# Dual_signal_switch.net
KiCad netlist of a schematic drawn in Altium Designer
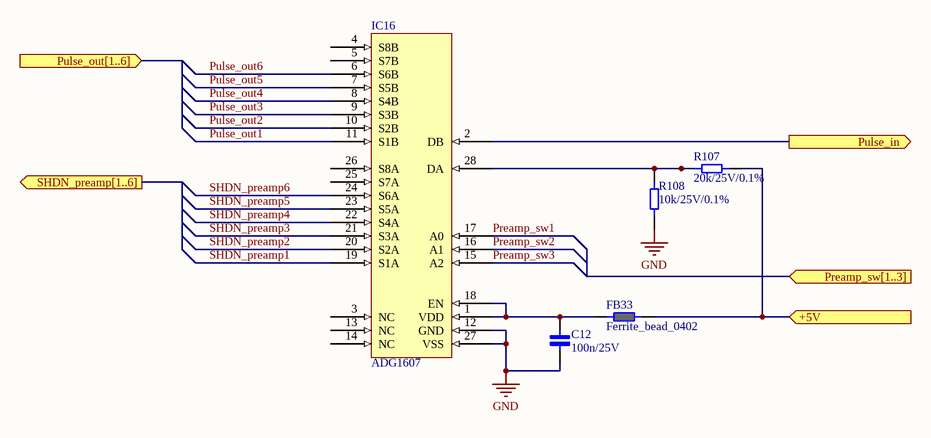
[diagram p0: Dual_signal_switch.SchDoc]

(export (version "E")
  (design (tool "Eeschema 10.0.6"))
  (components
    (comp (ref "C12")
      (value "100n/25V")
      (footprint "Cap_0402")
      (description "Ceramic Capacitor 100n / 0402 / 25V / ±5%, Wurth Elektronik MLCC")
      (libsource (lib "Cubesat_lib") (part "Cap_0402_100n"))
    )
    (comp (ref "FB33")
      (value "Ferrite_bead_0402")
      (footprint "FERRITE_0402")
      (description "Ferrite bead, wurth 74269241102")
      (libsource (lib "Cubesat_lib") (part "Ferrite_bead_0402"))
    )
    (comp (ref "IC16")
      (value "ADG1607")
      (footprint "TSOP28")
      (description "8-ch MUX")
      (libsource (lib "Cubesat_lib") (part "ADG1607"))
    )
    (comp (ref "R107")
      (value "20k/25V/0.1%")
      (footprint "RES_0402")
      (description "Vishay, thin film resistor 20k/25V/0.1%")
      (libsource (lib "Cubesat_lib") (part "Res_0402_20k"))
    )
    (comp (ref "R108")
      (value "10k/25V/0.1%")
      (footprint "RES_0402")
      (description "Vishay, thin film resistor 10k/25V/0.1%")
      (libsource (lib "Cubesat_lib") (part "Res_0402_10k"))
    )
  )
  (nets
    (net (code "1") (name "/+5V") (class "Default")
      (node (ref "FB33") (pin "2") (pinfunction "2_2") (pintype "passive"))
      (node (ref "R107") (pin "2") (pinfunction "2_2") (pintype "passive"))
    )
    (net (code "2") (name "/Preamp_sw1") (class "Default")
      (node (ref "IC16") (pin "17") (pinfunction "A0_17") (pintype "input"))
    )
    (net (code "3") (name "/Preamp_sw2") (class "Default")
      (node (ref "IC16") (pin "16") (pinfunction "A1_16") (pintype "input"))
    )
    (net (code "4") (name "/Preamp_sw3") (class "Default")
      (node (ref "IC16") (pin "15") (pinfunction "A2_15") (pintype "input"))
    )
    (net (code "6") (name "/Pulse_in") (class "Default")
      (node (ref "IC16") (pin "2") (pinfunction "DB_2") (pintype "input"))
    )
    (net (code "7") (name "/Pulse_out1") (class "Default")
      (node (ref "IC16") (pin "11") (pinfunction "S1B_11") (pintype "input"))
    )
    (net (code "8") (name "/Pulse_out2") (class "Default")
      (node (ref "IC16") (pin "10") (pinfunction "S2B_10") (pintype "input"))
    )
    (net (code "9") (name "/Pulse_out3") (class "Default")
      (node (ref "IC16") (pin "9") (pinfunction "S3B_9") (pintype "input"))
    )
    (net (code "10") (name "/Pulse_out4") (class "Default")
      (node (ref "IC16") (pin "8") (pinfunction "S4B_8") (pintype "input"))
    )
    (net (code "11") (name "/Pulse_out5") (class "Default")
      (node (ref "IC16") (pin "7") (pinfunction "S5B_7") (pintype "input"))
    )
    (net (code "12") (name "/Pulse_out6") (class "Default")
      (node (ref "IC16") (pin "6") (pinfunction "S6B_6") (pintype "input"))
    )
    (net (code "14") (name "/SHDN_preamp1") (class "Default")
      (node (ref "IC16") (pin "19") (pinfunction "S1A_19") (pintype "input"))
    )
    (net (code "15") (name "/SHDN_preamp2") (class "Default")
      (node (ref "IC16") (pin "20") (pinfunction "S2A_20") (pintype "input"))
    )
    (net (code "16") (name "/SHDN_preamp3") (class "Default")
      (node (ref "IC16") (pin "21") (pinfunction "S3A_21") (pintype "input"))
    )
    (net (code "17") (name "/SHDN_preamp4") (class "Default")
      (node (ref "IC16") (pin "22") (pinfunction "S4A_22") (pintype "input"))
    )
    (net (code "18") (name "/SHDN_preamp5") (class "Default")
      (node (ref "IC16") (pin "23") (pinfunction "S5A_23") (pintype "input"))
    )
    (net (code "19") (name "/SHDN_preamp6") (class "Default")
      (node (ref "IC16") (pin "24") (pinfunction "S6A_24") (pintype "input"))
    )
    (net (code "21") (name "GND") (class "Default")
      (node (ref "C12") (pin "1") (pinfunction "1_1") (pintype "passive"))
      (node (ref "IC16") (pin "12") (pinfunction "GND_12") (pintype "input"))
      (node (ref "IC16") (pin "27") (pinfunction "VSS_27") (pintype "input"))
      (node (ref "R108") (pin "1") (pinfunction "1_1") (pintype "passive"))
    )
    (net (code "22") (name "Net-(IC16-DA)") (class "Default")
      (node (ref "IC16") (pin "28") (pinfunction "DA_28") (pintype "input"))
      (node (ref "R107") (pin "1") (pinfunction "1_1") (pintype "passive"))
      (node (ref "R108") (pin "2") (pinfunction "2_2") (pintype "passive"))
    )
    (net (code "23") (name "Net-(IC16-EN)") (class "Default")
      (node (ref "C12") (pin "2") (pinfunction "2_2") (pintype "passive"))
      (node (ref "FB33") (pin "1") (pinfunction "1_1") (pintype "passive"))
      (node (ref "IC16") (pin "1") (pinfunction "VDD_1") (pintype "input"))
      (node (ref "IC16") (pin "18") (pinfunction "EN_18") (pintype "input"))
    )
    (net (code "24") (name "unconnected-(IC16-NC-Pad3)") (class "Default")
      (node (ref "IC16") (pin "3") (pinfunction "NC_3") (pintype "input"))
    )
    (net (code "25") (name "unconnected-(IC16-NC-Pad13)") (class "Default")
      (node (ref "IC16") (pin "13") (pinfunction "NC_13") (pintype "input"))
    )
    (net (code "26") (name "unconnected-(IC16-NC-Pad14)") (class "Default")
      (node (ref "IC16") (pin "14") (pinfunction "NC_14") (pintype "input"))
    )
    (net (code "27") (name "unconnected-(IC16-S7A-Pad25)") (class "Default")
      (node (ref "IC16") (pin "25") (pinfunction "S7A_25") (pintype "input"))
    )
    (net (code "28") (name "unconnected-(IC16-S7B-Pad5)") (class "Default")
      (node (ref "IC16") (pin "5") (pinfunction "S7B_5") (pintype "input"))
    )
    (net (code "29") (name "unconnected-(IC16-S8A-Pad26)") (class "Default")
      (node (ref "IC16") (pin "26") (pinfunction "S8A_26") (pintype "input"))
    )
    (net (code "30") (name "unconnected-(IC16-S8B-Pad4)") (class "Default")
      (node (ref "IC16") (pin "4") (pinfunction "S8B_4") (pintype "input"))
    )
  )
)
